# GPMAXMQ.net
KiCad netlist of a schematic drawn in Altium Designer
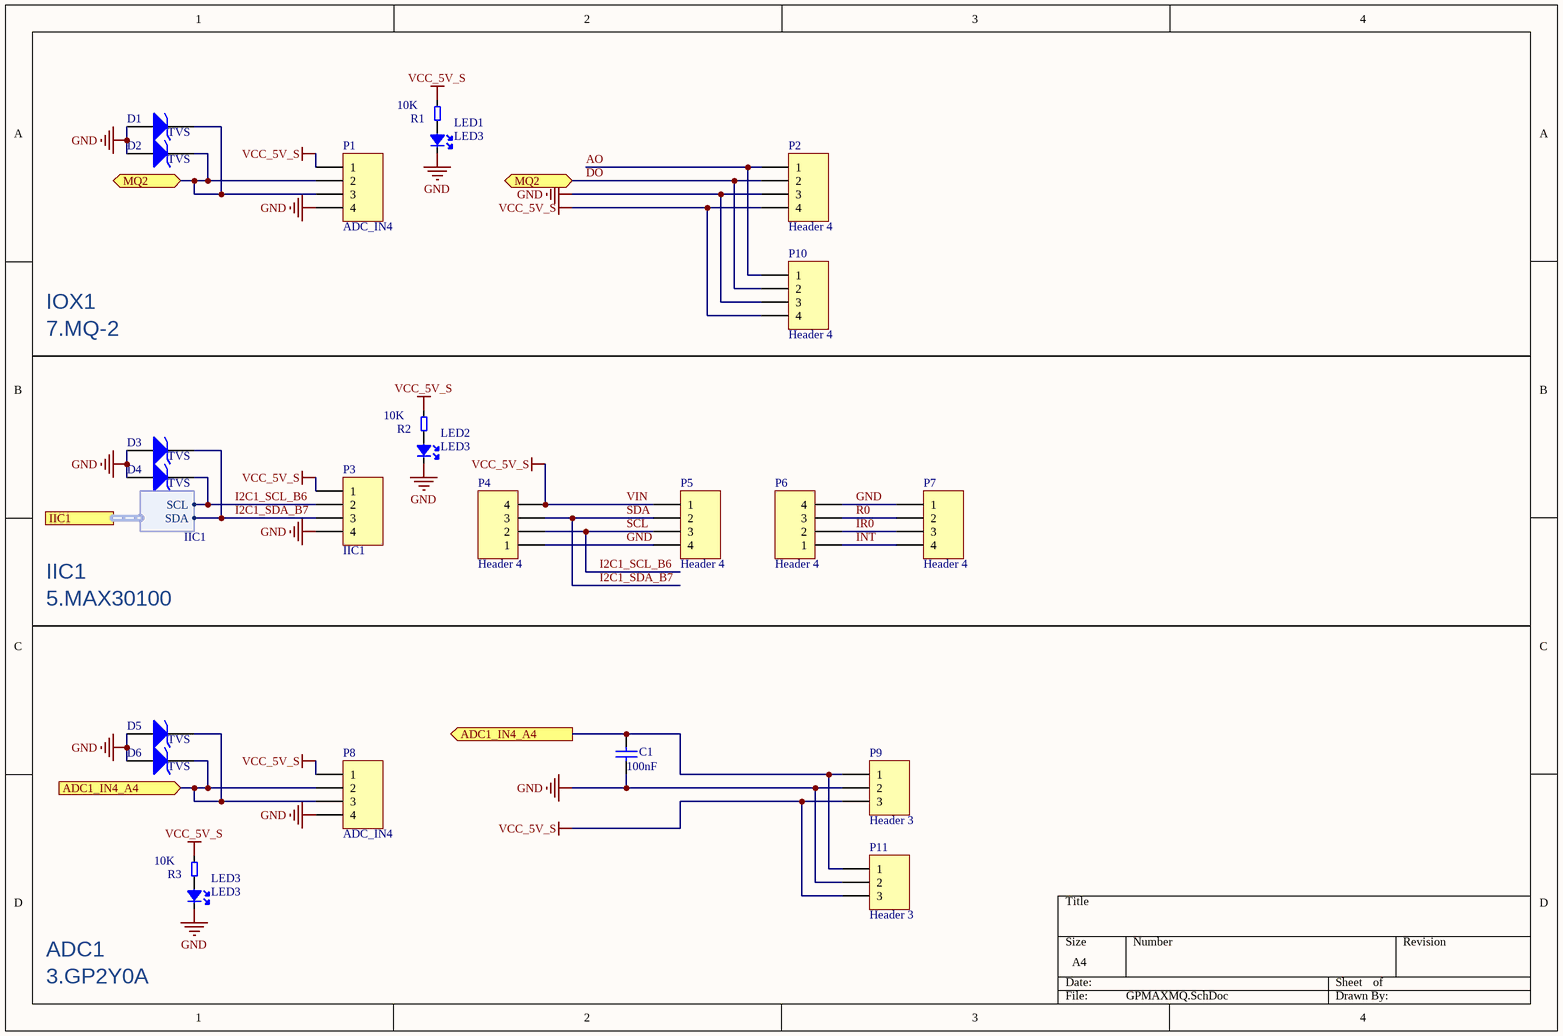
[diagram p0: GPMAXMQ.SchDoc]

(export (version "E")
  (design (tool "Eeschema 10.0.6"))
  (components
    (comp (ref "C1")
      (value "100nF")
      (footprint "C 0603_L")
      (fields (field (name "Comment") "CAP"))
      (libsource (lib "QT") (part "CAP"))
    )
    (comp (ref "D1")
      (value "TVS")
      (footprint "SOD-523")
      (description "High Conductance Fast Diode")
      (fields (field (name "PUBLISHER") "Altium Limited"))
      (libsource (lib "QT") (part "D"))
    )
    (comp (ref "D2")
      (value "TVS")
      (footprint "SOD-523")
      (description "High Conductance Fast Diode")
      (fields (field (name "PUBLISHER") "Altium Limited"))
      (libsource (lib "QT") (part "D"))
    )
    (comp (ref "D3")
      (value "TVS")
      (footprint "SOD-523")
      (description "High Conductance Fast Diode")
      (fields (field (name "PUBLISHER") "Altium Limited"))
      (libsource (lib "QT") (part "D"))
    )
    (comp (ref "D4")
      (value "TVS")
      (footprint "SOD-523")
      (description "High Conductance Fast Diode")
      (fields (field (name "PUBLISHER") "Altium Limited"))
      (libsource (lib "QT") (part "D"))
    )
    (comp (ref "D5")
      (value "TVS")
      (footprint "SOD-523")
      (description "High Conductance Fast Diode")
      (fields (field (name "PUBLISHER") "Altium Limited"))
      (libsource (lib "QT") (part "D"))
    )
    (comp (ref "D6")
      (value "TVS")
      (footprint "SOD-523")
      (description "High Conductance Fast Diode")
      (fields (field (name "PUBLISHER") "Altium Limited"))
      (libsource (lib "QT") (part "D"))
    )
    (comp (ref "LED1")
      (value "LED3")
      (footprint "0603-led")
      (description "DIODE LED")
      (libsource (lib "HXT-SCH") (part "CP_DIOLED"))
    )
    (comp (ref "LED2")
      (value "LED3")
      (footprint "0603-led")
      (description "DIODE LED")
      (libsource (lib "HXT-SCH") (part "CP_DIOLED"))
    )
    (comp (ref "LED3")
      (value "LED3")
      (footprint "0603-led")
      (description "DIODE LED")
      (libsource (lib "HXT-SCH") (part "CP_DIOLED"))
    )
    (comp (ref "P1")
      (value "ADC_IN4")
      (footprint "KF2EDGK-2.54-WI-4P")
      (description "Header, 4-Pin")
      (fields (field (name "PUBLISHER") "Altium Limited"))
      (libsource (lib "") (part "Header 4_1"))
    )
    (comp (ref "P2")
      (value "Header 4")
      (footprint "HDR2.54-LI-4P")
      (description "Header, 4-Pin")
      (fields (field (name "PUBLISHER") "Altium Limited"))
      (libsource (lib "") (part "Header 4_1"))
    )
    (comp (ref "P3")
      (value "IIC1")
      (footprint "KF2EDGK-2.54-WI-4P")
      (description "Header, 4-Pin")
      (fields (field (name "PUBLISHER") "Altium Limited"))
      (libsource (lib "") (part "Header 4_1"))
    )
    (comp (ref "P4")
      (value "Header 4")
      (footprint "HDR2.54-LI-4P")
      (description "Header, 4-Pin")
      (fields (field (name "PUBLISHER") "Altium Limited"))
      (libsource (lib "QT") (part "Header 4"))
    )
    (comp (ref "P5")
      (value "Header 4")
      (footprint "HDR2.54-LI-4P")
      (description "Header, 4-Pin")
      (fields (field (name "PUBLISHER") "Altium Limited"))
      (libsource (lib "") (part "Header 4_1"))
    )
    (comp (ref "P6")
      (value "Header 4")
      (footprint "HDR2.54-LI-4P")
      (description "Header, 4-Pin")
      (fields (field (name "PUBLISHER") "Altium Limited"))
      (libsource (lib "QT") (part "Header 4"))
    )
    (comp (ref "P7")
      (value "Header 4")
      (footprint "HDR2.54-LI-4P")
      (description "Header, 4-Pin")
      (fields (field (name "PUBLISHER") "Altium Limited"))
      (libsource (lib "") (part "Header 4_1"))
    )
    (comp (ref "P8")
      (value "ADC_IN4")
      (footprint "KF2EDGK-2.54-WI-4P")
      (description "Header, 4-Pin")
      (fields (field (name "PUBLISHER") "Altium Limited"))
      (libsource (lib "") (part "Header 4_1"))
    )
    (comp (ref "P9")
      (value "Header 3")
      (footprint "HDR2.54-LI-3P")
      (description "Header, 3-Pin")
      (fields (field (name "PUBLISHER") "Altium Limited"))
      (libsource (lib "QT") (part "Header 3"))
    )
    (comp (ref "P10")
      (value "Header 4")
      (footprint "HDR2.54-LI-4P")
      (description "Header, 4-Pin")
      (fields (field (name "PUBLISHER") "Altium Limited"))
      (libsource (lib "") (part "Header 4_1"))
    )
    (comp (ref "P11")
      (value "Header 3")
      (footprint "HDR2.54-LI-3P")
      (description "Header, 3-Pin")
      (fields (field (name "PUBLISHER") "Altium Limited"))
      (libsource (lib "QT") (part "Header 3"))
    )
    (comp (ref "R1") (value "10K") (footprint "0603") (libsource (lib "HXT-SCH") (part "RES2")))
    (comp (ref "R2") (value "10K") (footprint "0603") (libsource (lib "HXT-SCH") (part "RES2")))
    (comp (ref "R3") (value "10K") (footprint "0603") (libsource (lib "HXT-SCH") (part "RES2")))
  )
  (nets
    (net (code "2") (name "/ADC1_IN4_A4") (class "Default")
      (node (ref "C1") (pin "2") (pinfunction "2_2") (pintype "passive"))
      (node (ref "D5") (pin "2") (pinfunction "K_2") (pintype "passive"))
      (node (ref "D6") (pin "2") (pinfunction "K_2") (pintype "passive"))
      (node (ref "P11") (pin "1") (pinfunction "1_1") (pintype "passive"))
      (node (ref "P8") (pin "2") (pinfunction "2_2") (pintype "passive"))
      (node (ref "P8") (pin "3") (pinfunction "3_3") (pintype "passive"))
      (node (ref "P9") (pin "1") (pinfunction "1_1") (pintype "passive"))
    )
    (net (code "3") (name "/AO") (class "Default")
      (node (ref "P10") (pin "1") (pinfunction "1_1") (pintype "passive"))
      (node (ref "P2") (pin "1") (pinfunction "1_1") (pintype "passive"))
    )
    (net (code "4") (name "/DO") (class "Default")
      (node (ref "D1") (pin "2") (pinfunction "K_2") (pintype "passive"))
      (node (ref "D2") (pin "2") (pinfunction "K_2") (pintype "passive"))
      (node (ref "P1") (pin "2") (pinfunction "2_2") (pintype "passive"))
      (node (ref "P1") (pin "3") (pinfunction "3_3") (pintype "passive"))
      (node (ref "P10") (pin "2") (pinfunction "2_2") (pintype "passive"))
      (node (ref "P2") (pin "2") (pinfunction "2_2") (pintype "passive"))
    )
    (net (code "5") (name "/I2C1_SCL_B6") (class "Default")
      (node (ref "D4") (pin "2") (pinfunction "K_2") (pintype "passive"))
      (node (ref "P3") (pin "2") (pinfunction "2_2") (pintype "passive"))
      (node (ref "P4") (pin "2") (pinfunction "2_2") (pintype "passive"))
      (node (ref "P5") (pin "3") (pinfunction "3_3") (pintype "passive"))
    )
    (net (code "6") (name "/I2C1_SDA_B7") (class "Default")
      (node (ref "D3") (pin "2") (pinfunction "K_2") (pintype "passive"))
      (node (ref "P3") (pin "3") (pinfunction "3_3") (pintype "passive"))
      (node (ref "P4") (pin "3") (pinfunction "3_3") (pintype "passive"))
      (node (ref "P5") (pin "2") (pinfunction "2_2") (pintype "passive"))
    )
    (net (code "7") (name "/INT") (class "Default")
      (node (ref "P6") (pin "1") (pinfunction "1_1") (pintype "passive"))
      (node (ref "P7") (pin "4") (pinfunction "4_4") (pintype "passive"))
    )
    (net (code "8") (name "/IR0") (class "Default")
      (node (ref "P6") (pin "2") (pinfunction "2_2") (pintype "passive"))
      (node (ref "P7") (pin "3") (pinfunction "3_3") (pintype "passive"))
    )
    (net (code "9") (name "/R0") (class "Default")
      (node (ref "P6") (pin "3") (pinfunction "3_3") (pintype "passive"))
      (node (ref "P7") (pin "2") (pinfunction "2_2") (pintype "passive"))
    )
    (net (code "11") (name "GND") (class "Default")
      (node (ref "C1") (pin "1") (pinfunction "1_1") (pintype "passive"))
      (node (ref "D1") (pin "1") (pinfunction "A_1") (pintype "passive"))
      (node (ref "D2") (pin "1") (pinfunction "A_1") (pintype "passive"))
      (node (ref "D3") (pin "1") (pinfunction "A_1") (pintype "passive"))
      (node (ref "D4") (pin "1") (pinfunction "A_1") (pintype "passive"))
      (node (ref "D5") (pin "1") (pinfunction "A_1") (pintype "passive"))
      (node (ref "D6") (pin "1") (pinfunction "A_1") (pintype "passive"))
      (node (ref "LED1") (pin "2") (pinfunction "K_2") (pintype "passive"))
      (node (ref "LED2") (pin "2") (pinfunction "K_2") (pintype "passive"))
      (node (ref "LED3") (pin "2") (pinfunction "K_2") (pintype "passive"))
      (node (ref "P1") (pin "4") (pinfunction "4_4") (pintype "passive"))
      (node (ref "P10") (pin "3") (pinfunction "3_3") (pintype "passive"))
      (node (ref "P11") (pin "2") (pinfunction "2_2") (pintype "passive"))
      (node (ref "P2") (pin "3") (pinfunction "3_3") (pintype "passive"))
      (node (ref "P3") (pin "4") (pinfunction "4_4") (pintype "passive"))
      (node (ref "P4") (pin "1") (pinfunction "1_1") (pintype "passive"))
      (node (ref "P5") (pin "4") (pinfunction "4_4") (pintype "passive"))
      (node (ref "P6") (pin "4") (pinfunction "4_4") (pintype "passive"))
      (node (ref "P7") (pin "1") (pinfunction "1_1") (pintype "passive"))
      (node (ref "P8") (pin "4") (pinfunction "4_4") (pintype "passive"))
      (node (ref "P9") (pin "2") (pinfunction "2_2") (pintype "passive"))
    )
    (net (code "12") (name "Net-(LED1-A)") (class "Default")
      (node (ref "LED1") (pin "1") (pinfunction "A_1") (pintype "passive"))
      (node (ref "R1") (pin "1") (pinfunction "1_1") (pintype "passive"))
    )
    (net (code "13") (name "Net-(LED2-A)") (class "Default")
      (node (ref "LED2") (pin "1") (pinfunction "A_1") (pintype "passive"))
      (node (ref "R2") (pin "1") (pinfunction "1_1") (pintype "passive"))
    )
    (net (code "14") (name "Net-(LED3-A)") (class "Default")
      (node (ref "LED3") (pin "1") (pinfunction "A_1") (pintype "passive"))
      (node (ref "R3") (pin "1") (pinfunction "1_1") (pintype "passive"))
    )
    (net (code "15") (name "VCC_5V_S") (class "Default")
      (node (ref "P1") (pin "1") (pinfunction "1_1") (pintype "passive"))
      (node (ref "P10") (pin "4") (pinfunction "4_4") (pintype "passive"))
      (node (ref "P11") (pin "3") (pinfunction "3_3") (pintype "passive"))
      (node (ref "P2") (pin "4") (pinfunction "4_4") (pintype "passive"))
      (node (ref "P3") (pin "1") (pinfunction "1_1") (pintype "passive"))
      (node (ref "P4") (pin "4") (pinfunction "4_4") (pintype "passive"))
      (node (ref "P5") (pin "1") (pinfunction "1_1") (pintype "passive"))
      (node (ref "P8") (pin "1") (pinfunction "1_1") (pintype "passive"))
      (node (ref "P9") (pin "3") (pinfunction "3_3") (pintype "passive"))
      (node (ref "R1") (pin "2") (pinfunction "2_2") (pintype "passive"))
      (node (ref "R2") (pin "2") (pinfunction "2_2") (pintype "passive"))
      (node (ref "R3") (pin "2") (pinfunction "2_2") (pintype "passive"))
    )
  )
)
